# tx.net
KiCad netlist of a schematic drawn in EAGLE
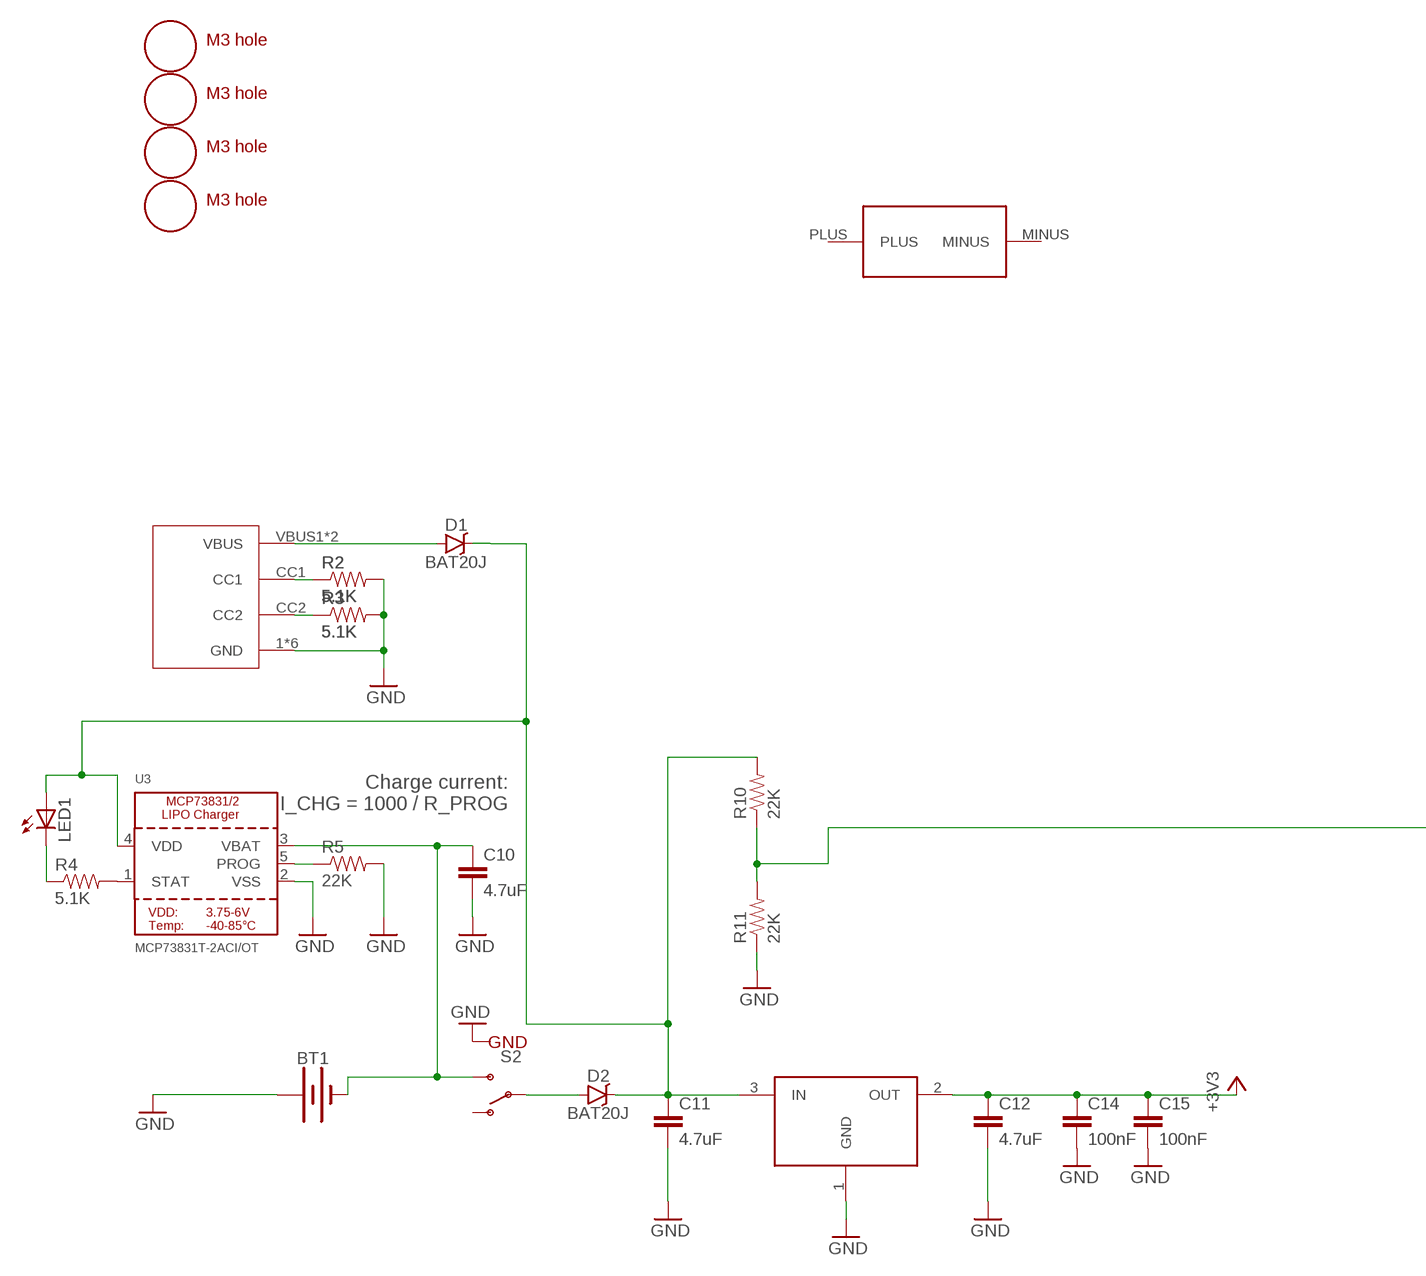
[diagram p0: schematic, sheet 1, part 1 of 2]
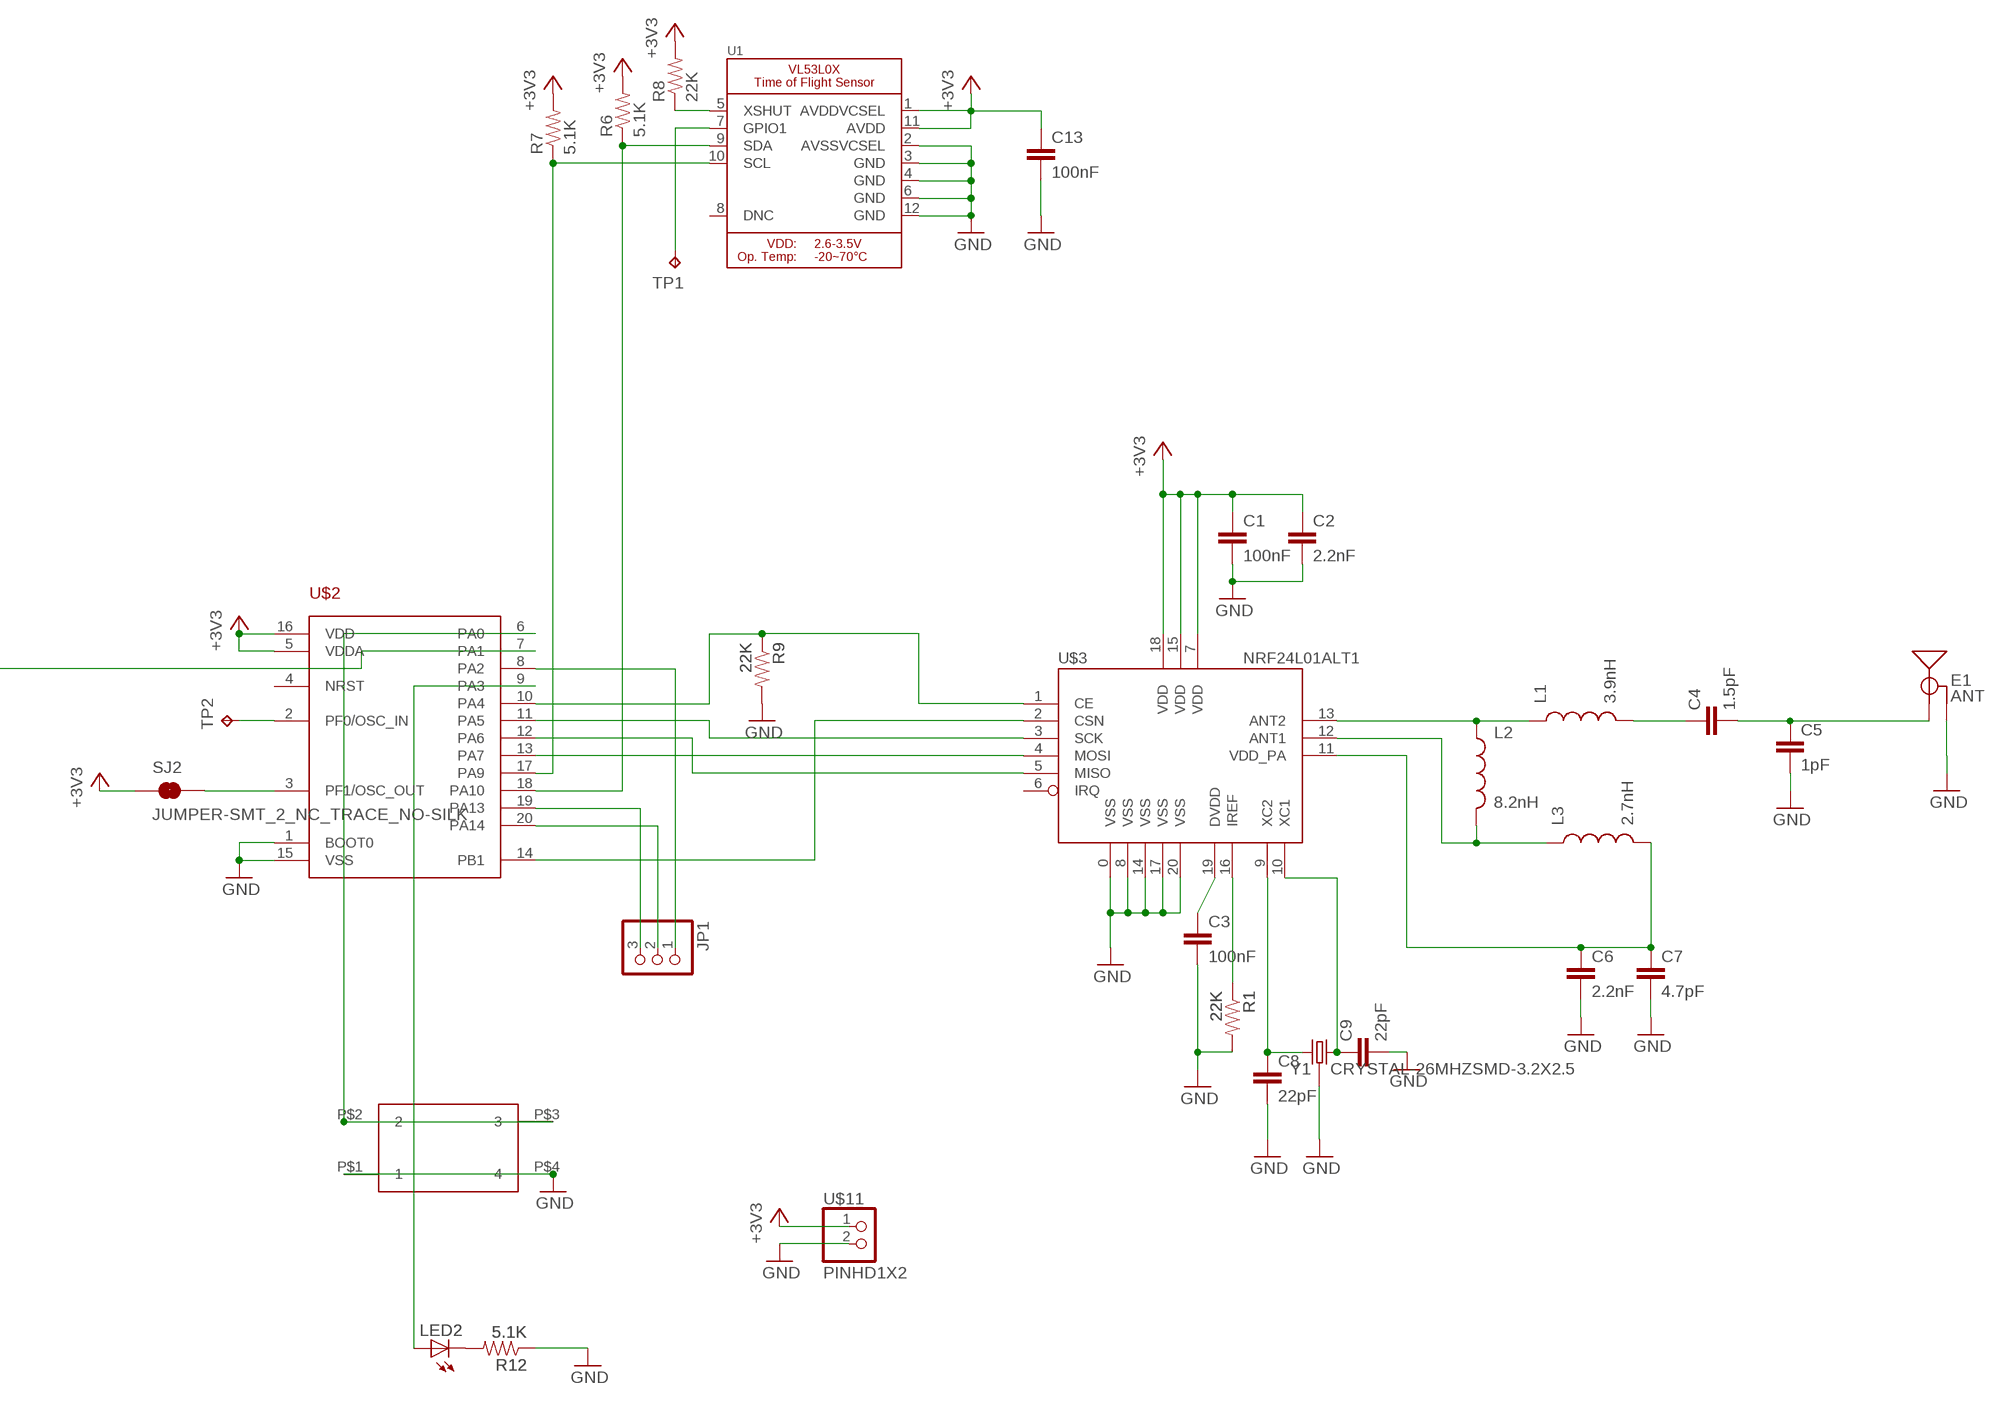
[diagram p1: schematic, sheet 1, part 2 of 2]

(export (version "E")
  (design (tool "Eeschema 10.0.6"))
  (components
    (comp (ref "BT1")
      (value "TX_SPARKFUN-BATTERIES_BATTERY-24.5MM_PTH")
      (footprint "eagle-import:TX_SPARKFUN-BATTERIES_BATTCON_24.5MM_PTH")
      (libsource (lib "eagle-import") (part "TX_SPARKFUN-BATTERIES_BATTERY-24.5MM_PTH"))
    )
    (comp (ref "C1")
      (value "100nF")
      (footprint "eagle-import:0805")
      (libsource (lib "eagle-import") (part "clock_CAP0805"))
    )
    (comp (ref "C2")
      (value "2.2nF")
      (footprint "eagle-import:0805")
      (libsource (lib "eagle-import") (part "clock_CAP0805"))
    )
    (comp (ref "C3")
      (value "100nF")
      (footprint "eagle-import:0805")
      (libsource (lib "eagle-import") (part "clock_CAP0805"))
    )
    (comp (ref "C4")
      (value "1.5pF")
      (footprint "eagle-import:0805")
      (libsource (lib "eagle-import") (part "clock_CAP0805"))
    )
    (comp (ref "C5")
      (value "1pF")
      (footprint "eagle-import:0805")
      (libsource (lib "eagle-import") (part "clock_CAP0805"))
    )
    (comp (ref "C6")
      (value "2.2nF")
      (footprint "eagle-import:0805")
      (libsource (lib "eagle-import") (part "clock_CAP0805"))
    )
    (comp (ref "C7")
      (value "4.7pF")
      (footprint "eagle-import:0805")
      (libsource (lib "eagle-import") (part "clock_CAP0805"))
    )
    (comp (ref "C8")
      (value "22pF")
      (footprint "eagle-import:0805")
      (libsource (lib "eagle-import") (part "clock_CAP0805"))
    )
    (comp (ref "C9")
      (value "22pF")
      (footprint "eagle-import:0805")
      (libsource (lib "eagle-import") (part "clock_CAP0805"))
    )
    (comp (ref "C10")
      (value "4.7uF")
      (footprint "eagle-import:0805")
      (libsource (lib "eagle-import") (part "CAP0805"))
    )
    (comp (ref "C11")
      (value "4.7uF")
      (footprint "eagle-import:0805")
      (libsource (lib "eagle-import") (part "clock_CAP0805"))
    )
    (comp (ref "C12")
      (value "4.7uF")
      (footprint "eagle-import:0805")
      (libsource (lib "eagle-import") (part "clock_CAP0805"))
    )
    (comp (ref "C13")
      (value "100nF")
      (footprint "eagle-import:0805")
      (libsource (lib "eagle-import") (part "clock_CAP0805"))
    )
    (comp (ref "C14")
      (value "100nF")
      (footprint "eagle-import:0805")
      (libsource (lib "eagle-import") (part "clock_CAP0805"))
    )
    (comp (ref "C15")
      (value "100nF")
      (footprint "eagle-import:0805")
      (libsource (lib "eagle-import") (part "clock_CAP0805"))
    )
    (comp (ref "D1")
      (value "BAT20J")
      (footprint "eagle-import:SOD-323")
      (libsource (lib "eagle-import") (part "DIODE-SCHOTTKY-BAT20J"))
    )
    (comp (ref "D2")
      (value "BAT20J")
      (footprint "eagle-import:SOD-323")
      (libsource (lib "eagle-import") (part "DIODE-SCHOTTKY-BAT20J"))
    )
    (comp (ref "E1")
      (value "ANT")
      (footprint "eagle-import:TRACE_ANTENNA_2.4GHZ_15.2MM")
      (libsource (lib "eagle-import") (part "ANTENNA-GROUNDEDTRACE-15.2MM"))
    )
    (comp (ref "JP1")
      (value "PINHD-1X3CB")
      (footprint "eagle-import:1X03-CLEANBIG")
      (libsource (lib "eagle-import") (part "PINHD-1X3CB"))
    )
    (comp (ref "L1")
      (value "3.9nH")
      (footprint "eagle-import:0805")
      (libsource (lib "eagle-import") (part "INDUCTOR0805"))
    )
    (comp (ref "L2")
      (value "8.2nH")
      (footprint "eagle-import:0805")
      (libsource (lib "eagle-import") (part "INDUCTOR0805"))
    )
    (comp (ref "L3")
      (value "2.7nH")
      (footprint "eagle-import:0805")
      (libsource (lib "eagle-import") (part "INDUCTOR0805"))
    )
    (comp (ref "LED1")
      (value "LEDCHIP-LED0805")
      (footprint "eagle-import:CHIP-LED0805")
      (libsource (lib "eagle-import") (part "LEDCHIP-LED0805"))
    )
    (comp (ref "LED2")
      (value "LEDCHIP-LED0805")
      (footprint "eagle-import:CHIP-LED0805")
      (libsource (lib "eagle-import") (part "LEDCHIP-LED0805"))
    )
    (comp (ref "R1")
      (value "22K")
      (footprint "eagle-import:0805")
      (libsource (lib "eagle-import") (part "joyAnalog_RESISTOR0805-RES"))
    )
    (comp (ref "R2")
      (value "5.1K")
      (footprint "eagle-import:0805")
      (libsource (lib "eagle-import") (part "joyAnalog_RESISTOR0805-RES"))
    )
    (comp (ref "R3")
      (value "5.1K")
      (footprint "eagle-import:0805")
      (libsource (lib "eagle-import") (part "joyAnalog_RESISTOR0805-RES"))
    )
    (comp (ref "R4")
      (value "5.1K")
      (footprint "eagle-import:0805")
      (libsource (lib "eagle-import") (part "RESISTOR0805-RES"))
    )
    (comp (ref "R5")
      (value "22K")
      (footprint "eagle-import:0805")
      (libsource (lib "eagle-import") (part "RESISTOR0805-RES"))
    )
    (comp (ref "R6")
      (value "5.1K")
      (footprint "eagle-import:0805")
      (libsource (lib "eagle-import") (part "RESISTOR0805-RES"))
    )
    (comp (ref "R7")
      (value "5.1K")
      (footprint "eagle-import:0805")
      (libsource (lib "eagle-import") (part "RESISTOR0805-RES"))
    )
    (comp (ref "R8")
      (value "22K")
      (footprint "eagle-import:0805")
      (libsource (lib "eagle-import") (part "RESISTOR0805-RES"))
    )
    (comp (ref "R9")
      (value "22K")
      (footprint "eagle-import:0805")
      (libsource (lib "eagle-import") (part "joyAnalog_RESISTOR0805-RES"))
    )
    (comp (ref "R10")
      (value "22K")
      (footprint "eagle-import:0805")
      (libsource (lib "eagle-import") (part "RESISTOR0805-RES"))
    )
    (comp (ref "R11")
      (value "22K")
      (footprint "eagle-import:0805")
      (libsource (lib "eagle-import") (part "RESISTOR0805-RES"))
    )
    (comp (ref "R12")
      (value "5.1K")
      (footprint "eagle-import:0805")
      (libsource (lib "eagle-import") (part "joyAnalog_RESISTOR0805-RES"))
    )
    (comp (ref "S2")
      (value "SWITCH-SPDTTDFGDFG")
      (footprint "eagle-import:SWITCH-SPST-SMD-A")
      (libsource (lib "eagle-import") (part "SWITCH-SPDTTDFGDFG"))
    )
    (comp (ref "SJ2")
      (value "JUMPER-SMT_2_NC_TRACE_NO-SILK")
      (footprint "eagle-import:SMT-JUMPER_2_NC_TRACE_NO-SILK")
      (libsource (lib "eagle-import") (part "JUMPER-SMT_2_NC_TRACE_NO-SILK"))
    )
    (comp (ref "TP1")
      (value "TPTP12R")
      (footprint "eagle-import:TP12R")
      (libsource (lib "eagle-import") (part "TPTP12R"))
    )
    (comp (ref "TP2")
      (value "TPTP12R")
      (footprint "eagle-import:TP12R")
      (libsource (lib "eagle-import") (part "TPTP12R"))
    )
    (comp (ref "U$1")
      (value "L1_USBC_6P_DEV")
      (footprint "eagle-import:L1_USBC_6P_PAC")
      (libsource (lib "eagle-import") (part "L1_USBC_6P_DEV"))
    )
    (comp (ref "U$2")
      (value "STM32F030F4")
      (footprint "eagle-import:TSSOP20")
      (libsource (lib "eagle-import") (part "STM32F030F4"))
    )
    (comp (ref "U$3")
      (value "NRF24L01ALT1")
      (footprint "eagle-import:QFN20_ALT1")
      (libsource (lib "eagle-import") (part "NRF24L01ALT1"))
    )
    (comp (ref "U$4")
      (value "AAA_SYM")
      (footprint "eagle-import:AAAWTF")
      (libsource (lib "eagle-import") (part "AAA_SYM"))
    )
    (comp (ref "U$5")
      (value "M3_MOUNTING_HOLE")
      (footprint "eagle-import:M3_MOUNTING_HOLE_PACK")
      (libsource (lib "eagle-import") (part "M3_MOUNTING_HOLE"))
    )
    (comp (ref "U$6")
      (value "M3_MOUNTING_HOLE")
      (footprint "eagle-import:M3_MOUNTING_HOLE_PACK")
      (libsource (lib "eagle-import") (part "M3_MOUNTING_HOLE"))
    )
    (comp (ref "U$7")
      (value "M3_MOUNTING_HOLE")
      (footprint "eagle-import:M3_MOUNTING_HOLE_PACK")
      (libsource (lib "eagle-import") (part "M3_MOUNTING_HOLE"))
    )
    (comp (ref "U$8")
      (value "M3_MOUNTING_HOLE")
      (footprint "eagle-import:M3_MOUNTING_HOLE_PACK")
      (libsource (lib "eagle-import") (part "M3_MOUNTING_HOLE"))
    )
    (comp (ref "U$9")
      (value "XC6206_DEV")
      (footprint "eagle-import:SOT23R_INFINEON")
      (libsource (lib "eagle-import") (part "XC6206_DEV"))
    )
    (comp (ref "U$10")
      (value "324_SW324_SWITCH_FOOT_HOLE")
      (footprint "eagle-import:342_SWICH_FOOT_HOLE")
      (libsource (lib "eagle-import") (part "324_SW324_SWITCH_FOOT_HOLE"))
    )
    (comp (ref "U$11")
      (value "PINHD1X2")
      (footprint "eagle-import:1X02")
      (libsource (lib "eagle-import") (part "PINHD1X2"))
    )
    (comp (ref "U1")
      (value "VL53L0X")
      (footprint "eagle-import:LGA12_ST")
      (libsource (lib "eagle-import") (part "VL53L0X"))
    )
    (comp (ref "U3")
      (value "MCP73831T-2ACI/OT")
      (footprint "eagle-import:SOT23-5")
      (libsource (lib "eagle-import") (part "MCP73831/2"))
    )
    (comp (ref "Y1")
      (value "CRYSTAL-26MHZSMD-3.2X2.5")
      (footprint "eagle-import:CRYSTAL-SMD-3.2X2.5MM")
      (libsource (lib "eagle-import") (part "CRYSTAL-26MHZSMD-3.2X2.5"))
    )
  )
  (nets
    (net (code "1") (name "+3V3") (class "Default")
      (node (ref "C1") (pin "1") (pinfunction "1_1") (pintype "passive"))
      (node (ref "C12") (pin "1") (pinfunction "1_1") (pintype "passive"))
      (node (ref "C13") (pin "1") (pinfunction "1_1") (pintype "passive"))
      (node (ref "C14") (pin "1") (pinfunction "1_1") (pintype "passive"))
      (node (ref "C15") (pin "1") (pinfunction "1_1") (pintype "passive"))
      (node (ref "C2") (pin "1") (pinfunction "1_1") (pintype "passive"))
      (node (ref "R6") (pin "2") (pinfunction "2_2") (pintype "passive"))
      (node (ref "R7") (pin "2") (pinfunction "2_2") (pintype "passive"))
      (node (ref "R8") (pin "2") (pinfunction "2_2") (pintype "passive"))
      (node (ref "SJ2") (pin "1") (pinfunction "1_1") (pintype "passive"))
      (node (ref "U$11") (pin "1") (pinfunction "1_1") (pintype "passive"))
      (node (ref "U$2") (pin "16") (pinfunction "VDD_16") (pintype "bidirectional"))
      (node (ref "U$2") (pin "5") (pinfunction "VDDA_5") (pintype "bidirectional"))
      (node (ref "U$3") (pin "15") (pinfunction "VDD_15") (pintype "power_in"))
      (node (ref "U$3") (pin "18") (pinfunction "VDD_18") (pintype "power_in"))
      (node (ref "U$3") (pin "7") (pinfunction "VDD_7") (pintype "power_in"))
      (node (ref "U$9") (pin "2") (pinfunction "OUT_2") (pintype "bidirectional"))
      (node (ref "U1") (pin "1") (pinfunction "AVDDVCSEL_1") (pintype "power_in"))
      (node (ref "U1") (pin "11") (pinfunction "AVDD_11") (pintype "power_in"))
    )
    (net (code "2") (name "GND") (class "Default")
      (node (ref "BT1") (pin "2") (pinfunction "+_2") (pintype "power_in"))
      (node (ref "C1") (pin "2") (pinfunction "2_2") (pintype "passive"))
      (node (ref "C10") (pin "2") (pinfunction "2_2") (pintype "passive"))
      (node (ref "C11") (pin "2") (pinfunction "2_2") (pintype "passive"))
      (node (ref "C12") (pin "2") (pinfunction "2_2") (pintype "passive"))
      (node (ref "C13") (pin "2") (pinfunction "2_2") (pintype "passive"))
      (node (ref "C14") (pin "2") (pinfunction "2_2") (pintype "passive"))
      (node (ref "C15") (pin "2") (pinfunction "2_2") (pintype "passive"))
      (node (ref "C2") (pin "2") (pinfunction "2_2") (pintype "passive"))
      (node (ref "C3") (pin "2") (pinfunction "2_2") (pintype "passive"))
      (node (ref "C5") (pin "2") (pinfunction "2_2") (pintype "passive"))
      (node (ref "C6") (pin "2") (pinfunction "2_2") (pintype "passive"))
      (node (ref "C7") (pin "2") (pinfunction "2_2") (pintype "passive"))
      (node (ref "C8") (pin "2") (pinfunction "2_2") (pintype "passive"))
      (node (ref "C9") (pin "2") (pinfunction "2_2") (pintype "passive"))
      (node (ref "E1") (pin "GND") (pinfunction "GND_GND") (pintype "bidirectional"))
      (node (ref "R1") (pin "2") (pinfunction "2_2") (pintype "passive"))
      (node (ref "R11") (pin "1") (pinfunction "1_1") (pintype "passive"))
      (node (ref "R12") (pin "1") (pinfunction "1_1") (pintype "passive"))
      (node (ref "R2") (pin "2") (pinfunction "2_2") (pintype "passive"))
      (node (ref "R3") (pin "2") (pinfunction "2_2") (pintype "passive"))
      (node (ref "R5") (pin "2") (pinfunction "2_2") (pintype "passive"))
      (node (ref "R9") (pin "2") (pinfunction "2_2") (pintype "passive"))
      (node (ref "S2") (pin "G1") (pinfunction "GND_G1") (pintype "passive"))
      (node (ref "S2") (pin "G2") (pinfunction "GND_G2") (pintype "passive"))
      (node (ref "S2") (pin "G3") (pinfunction "GND_G3") (pintype "passive"))
      (node (ref "S2") (pin "G4") (pinfunction "GND_G4") (pintype "passive"))
      (node (ref "U$1") (pin "1") (pinfunction "GND_1") (pintype "bidirectional"))
      (node (ref "U$1") (pin "2") (pinfunction "GND_2") (pintype "bidirectional"))
      (node (ref "U$1") (pin "3") (pinfunction "GND_3") (pintype "bidirectional"))
      (node (ref "U$1") (pin "4") (pinfunction "GND_4") (pintype "bidirectional"))
      (node (ref "U$1") (pin "GND1") (pinfunction "GND_GND1") (pintype "bidirectional"))
      (node (ref "U$1") (pin "GND2") (pinfunction "GND_GND2") (pintype "bidirectional"))
      (node (ref "U$10") (pin "P$1") (pinfunction "1_P$1") (pintype "bidirectional"))
      (node (ref "U$10") (pin "P$4") (pinfunction "4_P$4") (pintype "bidirectional"))
      (node (ref "U$11") (pin "2") (pinfunction "2_2") (pintype "passive"))
      (node (ref "U$2") (pin "1") (pinfunction "BOOT0_1") (pintype "bidirectional"))
      (node (ref "U$2") (pin "15") (pinfunction "VSS_15") (pintype "bidirectional"))
      (node (ref "U$3") (pin "0") (pinfunction "VSS_0") (pintype "power_in"))
      (node (ref "U$3") (pin "14") (pinfunction "VSS_14") (pintype "power_in"))
      (node (ref "U$3") (pin "17") (pinfunction "VSS_17") (pintype "power_in"))
      (node (ref "U$3") (pin "20") (pinfunction "VSS_20") (pintype "power_in"))
      (node (ref "U$3") (pin "8") (pinfunction "VSS_8") (pintype "power_in"))
      (node (ref "U$9") (pin "1") (pinfunction "GND_1") (pintype "bidirectional"))
      (node (ref "U1") (pin "12") (pinfunction "GND_12") (pintype "power_in"))
      (node (ref "U1") (pin "2") (pinfunction "AVSSVCSEL_2") (pintype "power_in"))
      (node (ref "U1") (pin "3") (pinfunction "GND_3") (pintype "power_in"))
      (node (ref "U1") (pin "4") (pinfunction "GND_4") (pintype "power_in"))
      (node (ref "U1") (pin "6") (pinfunction "GND_6") (pintype "power_in"))
      (node (ref "U3") (pin "2") (pinfunction "VSS_2") (pintype "power_in"))
      (node (ref "Y1") (pin "2") (pinfunction "3_2") (pintype "passive"))
      (node (ref "Y1") (pin "4") (pinfunction "3_4") (pintype "passive"))
    )
    (net (code "3") (name "Net-(BT1--)") (class "Default")
      (node (ref "BT1") (pin "1") (pinfunction "-_1") (pintype "power_in"))
      (node (ref "C10") (pin "1") (pinfunction "1_1") (pintype "passive"))
      (node (ref "S2") (pin "3") (pinfunction "S_3") (pintype "passive"))
      (node (ref "U3") (pin "3") (pinfunction "VBAT_3") (pintype "power_in"))
    )
    (net (code "4") (name "Net-(C4-Pad1)") (class "Default")
      (node (ref "C4") (pin "1") (pinfunction "1_1") (pintype "passive"))
      (node (ref "L1") (pin "2") (pinfunction "2_2") (pintype "passive"))
    )
    (net (code "5") (name "Net-(D1-PadA)") (class "Default")
      (node (ref "D1") (pin "A") (pinfunction "A_A") (pintype "passive"))
      (node (ref "U$1") (pin "VBUS1") (pinfunction "VBUS_VBUS1") (pintype "bidirectional"))
      (node (ref "U$1") (pin "VBUS2") (pinfunction "VBUS_VBUS2") (pintype "bidirectional"))
    )
    (net (code "6") (name "Net-(E1-SIGNAL)") (class "Default")
      (node (ref "C4") (pin "2") (pinfunction "2_2") (pintype "passive"))
      (node (ref "C5") (pin "1") (pinfunction "1_1") (pintype "passive"))
      (node (ref "E1") (pin "ANT") (pinfunction "SIGNAL_ANT") (pintype "bidirectional"))
    )
    (net (code "7") (name "Net-(LED1-PadC)") (class "Default")
      (node (ref "LED1") (pin "C") (pinfunction "C_C") (pintype "passive"))
      (node (ref "R4") (pin "1") (pinfunction "1_1") (pintype "passive"))
    )
    (net (code "8") (name "Net-(LED2-PadC)") (class "Default")
      (node (ref "LED2") (pin "C") (pinfunction "C_C") (pintype "passive"))
      (node (ref "R12") (pin "2") (pinfunction "2_2") (pintype "passive"))
    )
    (net (code "9") (name "Net-(R2-Pad1)") (class "Default")
      (node (ref "R2") (pin "1") (pinfunction "1_1") (pintype "passive"))
      (node (ref "U$1") (pin "CC1") (pinfunction "CC1_CC1") (pintype "bidirectional"))
    )
    (net (code "10") (name "Net-(R3-Pad1)") (class "Default")
      (node (ref "R3") (pin "1") (pinfunction "1_1") (pintype "passive"))
      (node (ref "U$1") (pin "CC2") (pinfunction "CC2_CC2") (pintype "bidirectional"))
    )
    (net (code "11") (name "Net-(S2-P)") (class "Default")
      (node (ref "D2") (pin "A") (pinfunction "A_A") (pintype "passive"))
      (node (ref "S2") (pin "2") (pinfunction "P_2") (pintype "passive"))
    )
    (net (code "12") (name "Net-(U$2-PA1)") (class "Default")
      (node (ref "R10") (pin "1") (pinfunction "1_1") (pintype "passive"))
      (node (ref "R11") (pin "2") (pinfunction "2_2") (pintype "passive"))
      (node (ref "U$2") (pin "7") (pinfunction "PA1_7") (pintype "bidirectional"))
    )
    (net (code "13") (name "Net-(U$2-PA2)") (class "Default")
      (node (ref "JP1") (pin "1") (pinfunction "1_1") (pintype "passive"))
      (node (ref "U$2") (pin "8") (pinfunction "PA2_8") (pintype "bidirectional"))
    )
    (net (code "14") (name "Net-(U$2-PA3)") (class "Default")
      (node (ref "LED2") (pin "A") (pinfunction "A_A") (pintype "passive"))
      (node (ref "U$2") (pin "9") (pinfunction "PA3_9") (pintype "bidirectional"))
    )
    (net (code "15") (name "Net-(U$2-PA4)") (class "Default")
      (node (ref "R9") (pin "1") (pinfunction "1_1") (pintype "passive"))
      (node (ref "U$2") (pin "10") (pinfunction "PA4_10") (pintype "bidirectional"))
      (node (ref "U$3") (pin "1") (pinfunction "CE_1") (pintype "input"))
    )
    (net (code "16") (name "Net-(U$2-PA5)") (class "Default")
      (node (ref "U$2") (pin "11") (pinfunction "PA5_11") (pintype "bidirectional"))
      (node (ref "U$3") (pin "3") (pinfunction "SCK_3") (pintype "input"))
    )
    (net (code "17") (name "Net-(U$2-PA6)") (class "Default")
      (node (ref "U$2") (pin "12") (pinfunction "PA6_12") (pintype "bidirectional"))
      (node (ref "U$3") (pin "5") (pinfunction "MISO_5") (pintype "output"))
    )
    (net (code "18") (name "Net-(U$2-PA7)") (class "Default")
      (node (ref "U$2") (pin "13") (pinfunction "PA7_13") (pintype "bidirectional"))
      (node (ref "U$3") (pin "4") (pinfunction "MOSI_4") (pintype "input"))
    )
    (net (code "19") (name "Net-(U$2-PA9)") (class "Default")
      (node (ref "R7") (pin "1") (pinfunction "1_1") (pintype "passive"))
      (node (ref "U$2") (pin "17") (pinfunction "PA9_17") (pintype "bidirectional"))
      (node (ref "U1") (pin "10") (pinfunction "SCL_10") (pintype "open_collector"))
    )
    (net (code "20") (name "Net-(U$2-PA10)") (class "Default")
      (node (ref "R6") (pin "1") (pinfunction "1_1") (pintype "passive"))
      (node (ref "U$2") (pin "18") (pinfunction "PA10_18") (pintype "bidirectional"))
      (node (ref "U1") (pin "9") (pinfunction "SDA_9") (pintype "open_collector"))
    )
    (net (code "21") (name "Net-(U$2-PA13)") (class "Default")
      (node (ref "JP1") (pin "3") (pinfunction "3_3") (pintype "passive"))
      (node (ref "U$2") (pin "19") (pinfunction "PA13_19") (pintype "bidirectional"))
    )
    (net (code "22") (name "Net-(U$2-PA14)") (class "Default")
      (node (ref "JP1") (pin "2") (pinfunction "2_2") (pintype "passive"))
      (node (ref "U$2") (pin "20") (pinfunction "PA14_20") (pintype "bidirectional"))
    )
    (net (code "23") (name "Net-(U$2-PB1)") (class "Default")
      (node (ref "U$2") (pin "14") (pinfunction "PB1_14") (pintype "bidirectional"))
      (node (ref "U$3") (pin "2") (pinfunction "CSN_2") (pintype "input"))
    )
    (net (code "24") (name "Net-(U$2-PF0{slash}OSC_IN)") (class "Default")
      (node (ref "TP2") (pin "TP") (pinfunction "TP_TP") (pintype "input"))
      (node (ref "U$2") (pin "2") (pinfunction "PF0/OSC_IN_2") (pintype "bidirectional"))
    )
    (net (code "25") (name "Net-(U$2-PF1{slash}OSC_OUT)") (class "Default")
      (node (ref "SJ2") (pin "2") (pinfunction "2_2") (pintype "passive"))
      (node (ref "U$2") (pin "3") (pinfunction "PF1/OSC_OUT_3") (pintype "bidirectional"))
    )
    (net (code "26") (name "Net-(U$3-ANT1)") (class "Default")
      (node (ref "L2") (pin "2") (pinfunction "2_2") (pintype "passive"))
      (node (ref "L3") (pin "1") (pinfunction "1_1") (pintype "passive"))
      (node (ref "U$3") (pin "12") (pinfunction "ANT1_12") (pintype "output"))
    )
    (net (code "27") (name "Net-(U$3-ANT2)") (class "Default")
      (node (ref "L1") (pin "1") (pinfunction "1_1") (pintype "passive"))
      (node (ref "L2") (pin "1") (pinfunction "1_1") (pintype "passive"))
      (node (ref "U$3") (pin "13") (pinfunction "ANT2_13") (pintype "output"))
    )
    (net (code "28") (name "Net-(U$3-DVDD)") (class "Default")
      (node (ref "C3") (pin "1") (pinfunction "1_1") (pintype "passive"))
      (node (ref "U$3") (pin "19") (pinfunction "DVDD_19") (pintype "power_in"))
    )
    (net (code "29") (name "Net-(U$3-IREF)") (class "Default")
      (node (ref "R1") (pin "1") (pinfunction "1_1") (pintype "passive"))
      (node (ref "U$3") (pin "16") (pinfunction "IREF_16") (pintype "input"))
    )
    (net (code "30") (name "Net-(U$3-VDD_PA)") (class "Default")
      (node (ref "C6") (pin "1") (pinfunction "1_1") (pintype "passive"))
      (node (ref "C7") (pin "1") (pinfunction "1_1") (pintype "passive"))
      (node (ref "L3") (pin "2") (pinfunction "2_2") (pintype "passive"))
      (node (ref "U$3") (pin "11") (pinfunction "VDD_PA_11") (pintype "power_in"))
    )
    (net (code "31") (name "Net-(U$3-XC1)") (class "Default")
      (node (ref "C9") (pin "1") (pinfunction "1_1") (pintype "passive"))
      (node (ref "U$3") (pin "10") (pinfunction "XC1_10") (pintype "input"))
      (node (ref "Y1") (pin "3") (pinfunction "2_3") (pintype "passive"))
    )
    (net (code "32") (name "Net-(U$3-XC2)") (class "Default")
      (node (ref "C8") (pin "1") (pinfunction "1_1") (pintype "passive"))
      (node (ref "U$3") (pin "9") (pinfunction "XC2_9") (pintype "input"))
      (node (ref "Y1") (pin "1") (pinfunction "1_1") (pintype "passive"))
    )
    (net (code "33") (name "Net-(U$9-IN)") (class "Default")
      (node (ref "C11") (pin "1") (pinfunction "1_1") (pintype "passive"))
      (node (ref "D1") (pin "C") (pinfunction "C_C") (pintype "passive"))
      (node (ref "D2") (pin "C") (pinfunction "C_C") (pintype "passive"))
      (node (ref "LED1") (pin "A") (pinfunction "A_A") (pintype "passive"))
      (node (ref "R10") (pin "2") (pinfunction "2_2") (pintype "passive"))
      (node (ref "U$9") (pin "3") (pinfunction "IN_3") (pintype "bidirectional"))
      (node (ref "U3") (pin "4") (pinfunction "VDD_4") (pintype "power_in"))
    )
    (net (code "34") (name "Net-(U$10-2)") (class "Default")
      (node (ref "U$10") (pin "P$2") (pinfunction "2_P$2") (pintype "bidirectional"))
      (node (ref "U$10") (pin "P$3") (pinfunction "3_P$3") (pintype "bidirectional"))
      (node (ref "U$2") (pin "6") (pinfunction "PA0_6") (pintype "bidirectional"))
    )
    (net (code "35") (name "Net-(U1-GPIO1)") (class "Default")
      (node (ref "TP1") (pin "TP") (pinfunction "TP_TP") (pintype "input"))
      (node (ref "U1") (pin "7") (pinfunction "GPIO1_7") (pintype "output"))
    )
    (net (code "36") (name "Net-(U1-XSHUT)") (class "Default")
      (node (ref "R8") (pin "1") (pinfunction "1_1") (pintype "passive"))
      (node (ref "U1") (pin "5") (pinfunction "XSHUT_5") (pintype "input"))
    )
    (net (code "37") (name "Net-(U3-PROG)") (class "Default")
      (node (ref "R5") (pin "1") (pinfunction "1_1") (pintype "passive"))
      (node (ref "U3") (pin "5") (pinfunction "PROG_5") (pintype "input"))
    )
    (net (code "38") (name "Net-(U3-STAT)") (class "Default")
      (node (ref "R4") (pin "2") (pinfunction "2_2") (pintype "passive"))
      (node (ref "U3") (pin "1") (pinfunction "STAT_1") (pintype "output"))
    )
    (net (code "39") (name "unconnected-(S2-O-Pad1)") (class "Default")
      (node (ref "S2") (pin "1") (pinfunction "O_1") (pintype "passive"))
    )
    (net (code "40") (name "unconnected-(U$2-NRST-Pad4)") (class "Default")
      (node (ref "U$2") (pin "4") (pinfunction "NRST_4") (pintype "bidirectional"))
    )
    (net (code "41") (name "unconnected-(U$3-IRQ-Pad6)") (class "Default")
      (node (ref "U$3") (pin "6") (pinfunction "IRQ_6") (pintype "output"))
    )
    (net (code "42") (name "unconnected-(U$4-PadMINUS)") (class "Default")
      (node (ref "U$4") (pin "MINUS") (pinfunction "MINUS_MINUS") (pintype "bidirectional"))
    )
    (net (code "43") (name "unconnected-(U$4-PadPLUS)") (class "Default")
      (node (ref "U$4") (pin "PLUS") (pinfunction "PLUS_PLUS") (pintype "bidirectional"))
    )
    (net (code "44") (name "unconnected-(U1-DNC-Pad8)") (class "Default")
      (node (ref "U1") (pin "8") (pinfunction "DNC_8") (pintype "no_connect"))
    )
  )
)
